# MCU.net
KiCad netlist of a schematic drawn in Altium Designer
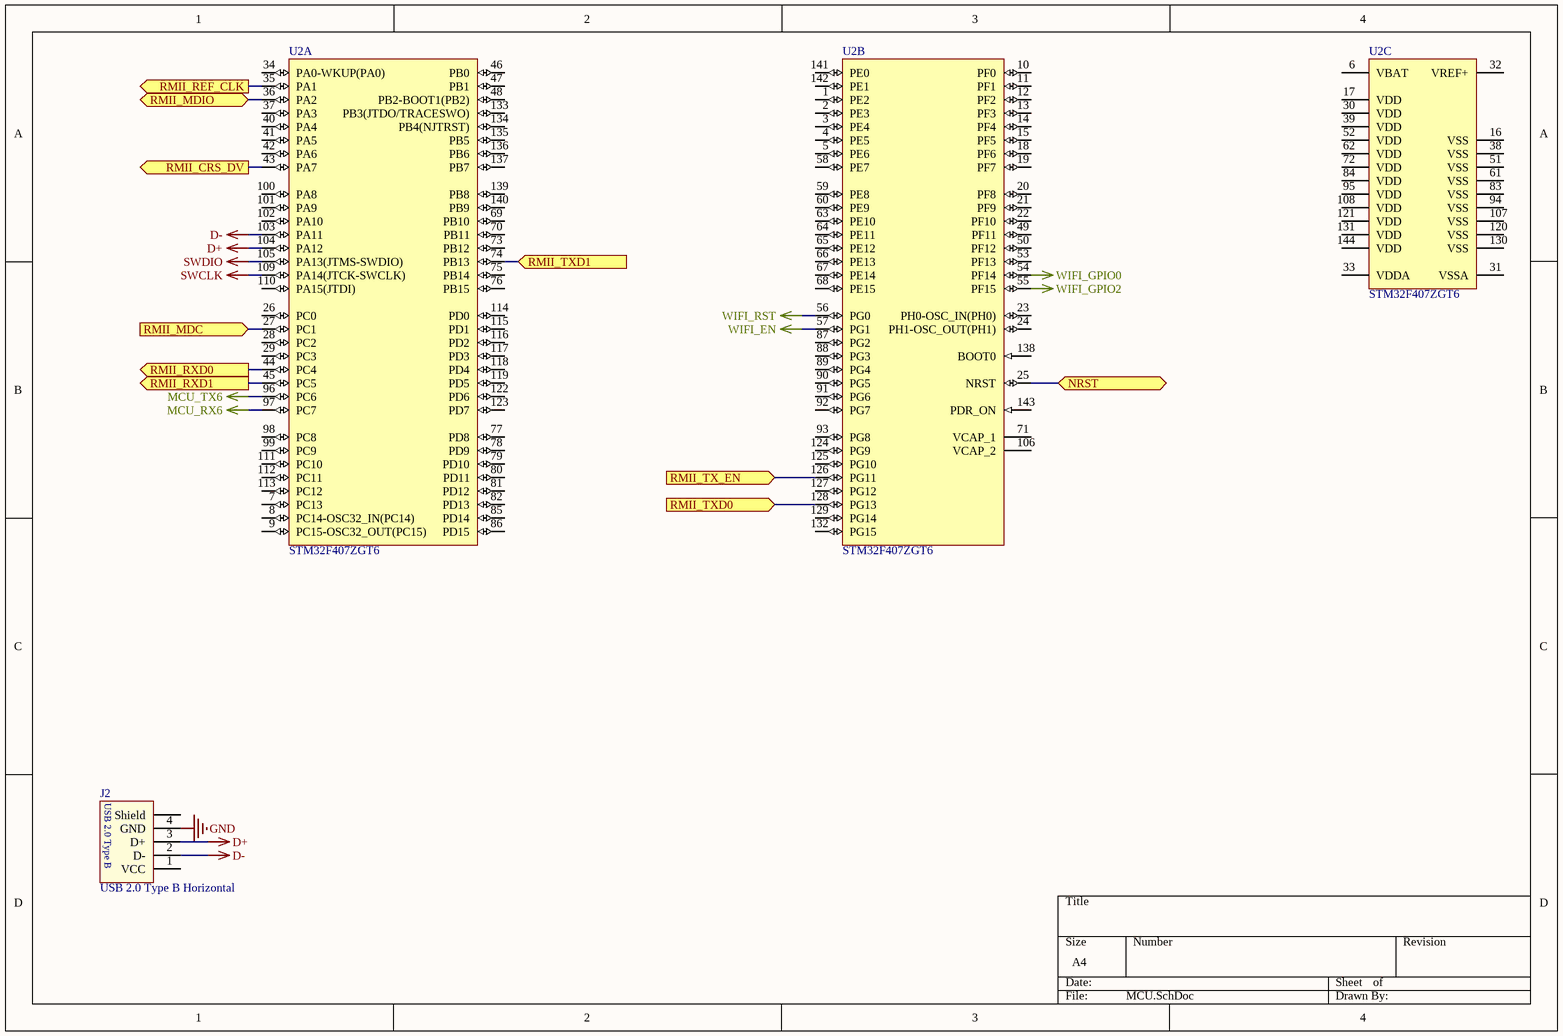
[diagram p0: MCU.SchDoc]

(export (version "E")
  (design (tool "Eeschema 10.0.6"))
  (components
    (comp (ref "J2")
      (value "USB 2.0 Type B Horizontal")
      (footprint "61400416121")
      (description "USB 2.0 Type B Horizontal WR-COM")
      (fields (field (name "PART NUMBER") "61400416121") (field (name "PUBLISHER") "Wurth Elektronik"))
      (libsource (lib "USB&HDMI") (part "USB 2.0 Type B Horizontal"))
    )
    (comp (ref "U2")
      (value "STM32F407ZGT6")
      (footprint "STM-LQFP144_N")
      (fields (field (name "MANUFACTURER") "STMicroelectronics"))
      (libsource (lib "STMicroelectronics STM32 F4") (part "STM32F407ZGT6"))
    )
  )
  (nets
    (net (code "1") (name "/NRST") (class "Default")
      (node (ref "U2") (pin "25") (pinfunction "NRST_25") (pintype "bidirectional"))
    )
    (net (code "2") (name "/RMII_CRS_DV") (class "Default")
      (node (ref "U2") (pin "43") (pinfunction "PA7_43") (pintype "bidirectional"))
    )
    (net (code "3") (name "/RMII_MDC") (class "Default")
      (node (ref "U2") (pin "27") (pinfunction "PC1_27") (pintype "bidirectional"))
    )
    (net (code "4") (name "/RMII_MDIO") (class "Default")
      (node (ref "U2") (pin "36") (pinfunction "PA2_36") (pintype "bidirectional"))
    )
    (net (code "5") (name "/RMII_REF_CLK") (class "Default")
      (node (ref "U2") (pin "35") (pinfunction "PA1_35") (pintype "bidirectional"))
    )
    (net (code "6") (name "/RMII_RXD0") (class "Default")
      (node (ref "U2") (pin "44") (pinfunction "PC4_44") (pintype "bidirectional"))
    )
    (net (code "7") (name "/RMII_RXD1") (class "Default")
      (node (ref "U2") (pin "45") (pinfunction "PC5_45") (pintype "bidirectional"))
    )
    (net (code "8") (name "/RMII_TXD0") (class "Default")
      (node (ref "U2") (pin "128") (pinfunction "PG13_128") (pintype "bidirectional"))
    )
    (net (code "9") (name "/RMII_TXD1") (class "Default")
      (node (ref "U2") (pin "74") (pinfunction "PB13_74") (pintype "bidirectional"))
    )
    (net (code "10") (name "/RMII_TX_EN") (class "Default")
      (node (ref "U2") (pin "126") (pinfunction "PG11_126") (pintype "bidirectional"))
    )
    (net (code "11") (name "D+") (class "Default")
      (node (ref "J2") (pin "3") (pinfunction "D+_3") (pintype "passive"))
      (node (ref "U2") (pin "104") (pinfunction "PA12_104") (pintype "bidirectional"))
    )
    (net (code "12") (name "D-") (class "Default")
      (node (ref "J2") (pin "2") (pinfunction "D-_2") (pintype "passive"))
      (node (ref "U2") (pin "103") (pinfunction "PA11_103") (pintype "bidirectional"))
    )
    (net (code "13") (name "GND") (class "Default")
      (node (ref "J2") (pin "4") (pinfunction "GND_4") (pintype "passive"))
    )
    (net (code "14") (name "MCU_RX6") (class "Default")
      (node (ref "U2") (pin "97") (pinfunction "PC7_97") (pintype "bidirectional"))
    )
    (net (code "15") (name "MCU_TX6") (class "Default")
      (node (ref "U2") (pin "96") (pinfunction "PC6_96") (pintype "bidirectional"))
    )
    (net (code "16") (name "SWCLK") (class "Default")
      (node (ref "U2") (pin "109") (pinfunction "PA14(JTCK-SWCLK)_109") (pintype "bidirectional"))
    )
    (net (code "17") (name "SWDIO") (class "Default")
      (node (ref "U2") (pin "105") (pinfunction "PA13(JTMS-SWDIO)_105") (pintype "bidirectional"))
    )
    (net (code "18") (name "WIFI_EN") (class "Default")
      (node (ref "U2") (pin "57") (pinfunction "PG1_57") (pintype "bidirectional"))
    )
    (net (code "19") (name "WIFI_GPIO0") (class "Default")
      (node (ref "U2") (pin "54") (pinfunction "PF14_54") (pintype "bidirectional"))
    )
    (net (code "20") (name "WIFI_GPIO2") (class "Default")
      (node (ref "U2") (pin "55") (pinfunction "PF15_55") (pintype "bidirectional"))
    )
    (net (code "21") (name "WIFI_RST") (class "Default")
      (node (ref "U2") (pin "56") (pinfunction "PG0_56") (pintype "bidirectional"))
    )
    (net (code "22") (name "unconnected-(J2-Shield-PadShell)") (class "Default")
      (node (ref "J2") (pin "Shell") (pinfunction "Shield_Shell") (pintype "passive"))
    )
    (net (code "23") (name "unconnected-(J2-VCC-Pad1)") (class "Default")
      (node (ref "J2") (pin "1") (pinfunction "VCC_1") (pintype "passive"))
    )
    (net (code "24") (name "unconnected-(U2A-PA0-WKUP(PA0)-Pad34)") (class "Default")
      (node (ref "U2") (pin "34") (pinfunction "PA0-WKUP(PA0)_34") (pintype "bidirectional"))
    )
    (net (code "25") (name "unconnected-(U2A-PA3-Pad37)") (class "Default")
      (node (ref "U2") (pin "37") (pinfunction "PA3_37") (pintype "bidirectional"))
    )
    (net (code "26") (name "unconnected-(U2A-PA4-Pad40)") (class "Default")
      (node (ref "U2") (pin "40") (pinfunction "PA4_40") (pintype "bidirectional"))
    )
    (net (code "27") (name "unconnected-(U2A-PA5-Pad41)") (class "Default")
      (node (ref "U2") (pin "41") (pinfunction "PA5_41") (pintype "bidirectional"))
    )
    (net (code "28") (name "unconnected-(U2A-PA6-Pad42)") (class "Default")
      (node (ref "U2") (pin "42") (pinfunction "PA6_42") (pintype "bidirectional"))
    )
    (net (code "29") (name "unconnected-(U2A-PA8-Pad100)") (class "Default")
      (node (ref "U2") (pin "100") (pinfunction "PA8_100") (pintype "bidirectional"))
    )
    (net (code "30") (name "unconnected-(U2A-PA9-Pad101)") (class "Default")
      (node (ref "U2") (pin "101") (pinfunction "PA9_101") (pintype "bidirectional"))
    )
    (net (code "31") (name "unconnected-(U2A-PA10-Pad102)") (class "Default")
      (node (ref "U2") (pin "102") (pinfunction "PA10_102") (pintype "bidirectional"))
    )
    (net (code "32") (name "unconnected-(U2A-PA15(JTDI)-Pad110)") (class "Default")
      (node (ref "U2") (pin "110") (pinfunction "PA15(JTDI)_110") (pintype "bidirectional"))
    )
    (net (code "33") (name "unconnected-(U2A-PB0-Pad46)") (class "Default")
      (node (ref "U2") (pin "46") (pinfunction "PB0_46") (pintype "bidirectional"))
    )
    (net (code "34") (name "unconnected-(U2A-PB1-Pad47)") (class "Default")
      (node (ref "U2") (pin "47") (pinfunction "PB1_47") (pintype "bidirectional"))
    )
    (net (code "35") (name "unconnected-(U2A-PB2-BOOT1(PB2)-Pad48)") (class "Default")
      (node (ref "U2") (pin "48") (pinfunction "PB2-BOOT1(PB2)_48") (pintype "bidirectional"))
    )
    (net (code "36") (name "unconnected-(U2A-PB3(JTDO{slash}TRACESWO)-Pad133)") (class "Default")
      (node (ref "U2") (pin "133") (pinfunction "PB3(JTDO/TRACESWO)_133") (pintype "bidirectional"))
    )
    (net (code "37") (name "unconnected-(U2A-PB4(NJTRST)-Pad134)") (class "Default")
      (node (ref "U2") (pin "134") (pinfunction "PB4(NJTRST)_134") (pintype "bidirectional"))
    )
    (net (code "38") (name "unconnected-(U2A-PB5-Pad135)") (class "Default")
      (node (ref "U2") (pin "135") (pinfunction "PB5_135") (pintype "bidirectional"))
    )
    (net (code "39") (name "unconnected-(U2A-PB6-Pad136)") (class "Default")
      (node (ref "U2") (pin "136") (pinfunction "PB6_136") (pintype "bidirectional"))
    )
    (net (code "40") (name "unconnected-(U2A-PB7-Pad137)") (class "Default")
      (node (ref "U2") (pin "137") (pinfunction "PB7_137") (pintype "bidirectional"))
    )
    (net (code "41") (name "unconnected-(U2A-PB8-Pad139)") (class "Default")
      (node (ref "U2") (pin "139") (pinfunction "PB8_139") (pintype "bidirectional"))
    )
    (net (code "42") (name "unconnected-(U2A-PB9-Pad140)") (class "Default")
      (node (ref "U2") (pin "140") (pinfunction "PB9_140") (pintype "bidirectional"))
    )
    (net (code "43") (name "unconnected-(U2A-PB10-Pad69)") (class "Default")
      (node (ref "U2") (pin "69") (pinfunction "PB10_69") (pintype "bidirectional"))
    )
    (net (code "44") (name "unconnected-(U2A-PB11-Pad70)") (class "Default")
      (node (ref "U2") (pin "70") (pinfunction "PB11_70") (pintype "bidirectional"))
    )
    (net (code "45") (name "unconnected-(U2A-PB12-Pad73)") (class "Default")
      (node (ref "U2") (pin "73") (pinfunction "PB12_73") (pintype "bidirectional"))
    )
    (net (code "46") (name "unconnected-(U2A-PB14-Pad75)") (class "Default")
      (node (ref "U2") (pin "75") (pinfunction "PB14_75") (pintype "bidirectional"))
    )
    (net (code "47") (name "unconnected-(U2A-PB15-Pad76)") (class "Default")
      (node (ref "U2") (pin "76") (pinfunction "PB15_76") (pintype "bidirectional"))
    )
    (net (code "48") (name "unconnected-(U2A-PC0-Pad26)") (class "Default")
      (node (ref "U2") (pin "26") (pinfunction "PC0_26") (pintype "bidirectional"))
    )
    (net (code "49") (name "unconnected-(U2A-PC2-Pad28)") (class "Default")
      (node (ref "U2") (pin "28") (pinfunction "PC2_28") (pintype "bidirectional"))
    )
    (net (code "50") (name "unconnected-(U2A-PC3-Pad29)") (class "Default")
      (node (ref "U2") (pin "29") (pinfunction "PC3_29") (pintype "bidirectional"))
    )
    (net (code "51") (name "unconnected-(U2A-PC8-Pad98)") (class "Default")
      (node (ref "U2") (pin "98") (pinfunction "PC8_98") (pintype "bidirectional"))
    )
    (net (code "52") (name "unconnected-(U2A-PC9-Pad99)") (class "Default")
      (node (ref "U2") (pin "99") (pinfunction "PC9_99") (pintype "bidirectional"))
    )
    (net (code "53") (name "unconnected-(U2A-PC10-Pad111)") (class "Default")
      (node (ref "U2") (pin "111") (pinfunction "PC10_111") (pintype "bidirectional"))
    )
    (net (code "54") (name "unconnected-(U2A-PC11-Pad112)") (class "Default")
      (node (ref "U2") (pin "112") (pinfunction "PC11_112") (pintype "bidirectional"))
    )
    (net (code "55") (name "unconnected-(U2A-PC12-Pad113)") (class "Default")
      (node (ref "U2") (pin "113") (pinfunction "PC12_113") (pintype "bidirectional"))
    )
    (net (code "56") (name "unconnected-(U2A-PC13-Pad7)") (class "Default")
      (node (ref "U2") (pin "7") (pinfunction "PC13_7") (pintype "bidirectional"))
    )
    (net (code "57") (name "unconnected-(U2A-PC14-OSC32_IN(PC14)-Pad8)") (class "Default")
      (node (ref "U2") (pin "8") (pinfunction "PC14-OSC32_IN(PC14)_8") (pintype "bidirectional"))
    )
    (net (code "58") (name "unconnected-(U2A-PC15-OSC32_OUT(PC15)-Pad9)") (class "Default")
      (node (ref "U2") (pin "9") (pinfunction "PC15-OSC32_OUT(PC15)_9") (pintype "bidirectional"))
    )
    (net (code "59") (name "unconnected-(U2A-PD0-Pad114)") (class "Default")
      (node (ref "U2") (pin "114") (pinfunction "PD0_114") (pintype "bidirectional"))
    )
    (net (code "60") (name "unconnected-(U2A-PD1-Pad115)") (class "Default")
      (node (ref "U2") (pin "115") (pinfunction "PD1_115") (pintype "bidirectional"))
    )
    (net (code "61") (name "unconnected-(U2A-PD2-Pad116)") (class "Default")
      (node (ref "U2") (pin "116") (pinfunction "PD2_116") (pintype "bidirectional"))
    )
    (net (code "62") (name "unconnected-(U2A-PD3-Pad117)") (class "Default")
      (node (ref "U2") (pin "117") (pinfunction "PD3_117") (pintype "bidirectional"))
    )
    (net (code "63") (name "unconnected-(U2A-PD4-Pad118)") (class "Default")
      (node (ref "U2") (pin "118") (pinfunction "PD4_118") (pintype "bidirectional"))
    )
    (net (code "64") (name "unconnected-(U2A-PD5-Pad119)") (class "Default")
      (node (ref "U2") (pin "119") (pinfunction "PD5_119") (pintype "bidirectional"))
    )
    (net (code "65") (name "unconnected-(U2A-PD6-Pad122)") (class "Default")
      (node (ref "U2") (pin "122") (pinfunction "PD6_122") (pintype "bidirectional"))
    )
    (net (code "66") (name "unconnected-(U2A-PD7-Pad123)") (class "Default")
      (node (ref "U2") (pin "123") (pinfunction "PD7_123") (pintype "bidirectional"))
    )
    (net (code "67") (name "unconnected-(U2A-PD8-Pad77)") (class "Default")
      (node (ref "U2") (pin "77") (pinfunction "PD8_77") (pintype "bidirectional"))
    )
    (net (code "68") (name "unconnected-(U2A-PD9-Pad78)") (class "Default")
      (node (ref "U2") (pin "78") (pinfunction "PD9_78") (pintype "bidirectional"))
    )
    (net (code "69") (name "unconnected-(U2A-PD10-Pad79)") (class "Default")
      (node (ref "U2") (pin "79") (pinfunction "PD10_79") (pintype "bidirectional"))
    )
    (net (code "70") (name "unconnected-(U2A-PD11-Pad80)") (class "Default")
      (node (ref "U2") (pin "80") (pinfunction "PD11_80") (pintype "bidirectional"))
    )
    (net (code "71") (name "unconnected-(U2A-PD12-Pad81)") (class "Default")
      (node (ref "U2") (pin "81") (pinfunction "PD12_81") (pintype "bidirectional"))
    )
    (net (code "72") (name "unconnected-(U2A-PD13-Pad82)") (class "Default")
      (node (ref "U2") (pin "82") (pinfunction "PD13_82") (pintype "bidirectional"))
    )
    (net (code "73") (name "unconnected-(U2A-PD14-Pad85)") (class "Default")
      (node (ref "U2") (pin "85") (pinfunction "PD14_85") (pintype "bidirectional"))
    )
    (net (code "74") (name "unconnected-(U2A-PD15-Pad86)") (class "Default")
      (node (ref "U2") (pin "86") (pinfunction "PD15_86") (pintype "bidirectional"))
    )
    (net (code "75") (name "unconnected-(U2B-BOOT0-Pad138)") (class "Default")
      (node (ref "U2") (pin "138") (pinfunction "BOOT0_138") (pintype "input"))
    )
    (net (code "76") (name "unconnected-(U2B-PDR_ON-Pad143)") (class "Default")
      (node (ref "U2") (pin "143") (pinfunction "PDR_ON_143") (pintype "input"))
    )
    (net (code "77") (name "unconnected-(U2B-PE0-Pad141)") (class "Default")
      (node (ref "U2") (pin "141") (pinfunction "PE0_141") (pintype "bidirectional"))
    )
    (net (code "78") (name "unconnected-(U2B-PE1-Pad142)") (class "Default")
      (node (ref "U2") (pin "142") (pinfunction "PE1_142") (pintype "bidirectional"))
    )
    (net (code "79") (name "unconnected-(U2B-PE2-Pad1)") (class "Default")
      (node (ref "U2") (pin "1") (pinfunction "PE2_1") (pintype "bidirectional"))
    )
    (net (code "80") (name "unconnected-(U2B-PE3-Pad2)") (class "Default")
      (node (ref "U2") (pin "2") (pinfunction "PE3_2") (pintype "bidirectional"))
    )
    (net (code "81") (name "unconnected-(U2B-PE4-Pad3)") (class "Default")
      (node (ref "U2") (pin "3") (pinfunction "PE4_3") (pintype "bidirectional"))
    )
    (net (code "82") (name "unconnected-(U2B-PE5-Pad4)") (class "Default")
      (node (ref "U2") (pin "4") (pinfunction "PE5_4") (pintype "bidirectional"))
    )
    (net (code "83") (name "unconnected-(U2B-PE6-Pad5)") (class "Default")
      (node (ref "U2") (pin "5") (pinfunction "PE6_5") (pintype "bidirectional"))
    )
    (net (code "84") (name "unconnected-(U2B-PE7-Pad58)") (class "Default")
      (node (ref "U2") (pin "58") (pinfunction "PE7_58") (pintype "bidirectional"))
    )
    (net (code "85") (name "unconnected-(U2B-PE8-Pad59)") (class "Default")
      (node (ref "U2") (pin "59") (pinfunction "PE8_59") (pintype "bidirectional"))
    )
    (net (code "86") (name "unconnected-(U2B-PE9-Pad60)") (class "Default")
      (node (ref "U2") (pin "60") (pinfunction "PE9_60") (pintype "bidirectional"))
    )
    (net (code "87") (name "unconnected-(U2B-PE10-Pad63)") (class "Default")
      (node (ref "U2") (pin "63") (pinfunction "PE10_63") (pintype "bidirectional"))
    )
    (net (code "88") (name "unconnected-(U2B-PE11-Pad64)") (class "Default")
      (node (ref "U2") (pin "64") (pinfunction "PE11_64") (pintype "bidirectional"))
    )
    (net (code "89") (name "unconnected-(U2B-PE12-Pad65)") (class "Default")
      (node (ref "U2") (pin "65") (pinfunction "PE12_65") (pintype "bidirectional"))
    )
    (net (code "90") (name "unconnected-(U2B-PE13-Pad66)") (class "Default")
      (node (ref "U2") (pin "66") (pinfunction "PE13_66") (pintype "bidirectional"))
    )
    (net (code "91") (name "unconnected-(U2B-PE14-Pad67)") (class "Default")
      (node (ref "U2") (pin "67") (pinfunction "PE14_67") (pintype "bidirectional"))
    )
    (net (code "92") (name "unconnected-(U2B-PE15-Pad68)") (class "Default")
      (node (ref "U2") (pin "68") (pinfunction "PE15_68") (pintype "bidirectional"))
    )
    (net (code "93") (name "unconnected-(U2B-PF0-Pad10)") (class "Default")
      (node (ref "U2") (pin "10") (pinfunction "PF0_10") (pintype "bidirectional"))
    )
    (net (code "94") (name "unconnected-(U2B-PF1-Pad11)") (class "Default")
      (node (ref "U2") (pin "11") (pinfunction "PF1_11") (pintype "bidirectional"))
    )
    (net (code "95") (name "unconnected-(U2B-PF2-Pad12)") (class "Default")
      (node (ref "U2") (pin "12") (pinfunction "PF2_12") (pintype "bidirectional"))
    )
    (net (code "96") (name "unconnected-(U2B-PF3-Pad13)") (class "Default")
      (node (ref "U2") (pin "13") (pinfunction "PF3_13") (pintype "bidirectional"))
    )
    (net (code "97") (name "unconnected-(U2B-PF4-Pad14)") (class "Default")
      (node (ref "U2") (pin "14") (pinfunction "PF4_14") (pintype "bidirectional"))
    )
    (net (code "98") (name "unconnected-(U2B-PF5-Pad15)") (class "Default")
      (node (ref "U2") (pin "15") (pinfunction "PF5_15") (pintype "bidirectional"))
    )
    (net (code "99") (name "unconnected-(U2B-PF6-Pad18)") (class "Default")
      (node (ref "U2") (pin "18") (pinfunction "PF6_18") (pintype "bidirectional"))
    )
    (net (code "100") (name "unconnected-(U2B-PF7-Pad19)") (class "Default")
      (node (ref "U2") (pin "19") (pinfunction "PF7_19") (pintype "bidirectional"))
    )
    (net (code "101") (name "unconnected-(U2B-PF8-Pad20)") (class "Default")
      (node (ref "U2") (pin "20") (pinfunction "PF8_20") (pintype "bidirectional"))
    )
    (net (code "102") (name "unconnected-(U2B-PF9-Pad21)") (class "Default")
      (node (ref "U2") (pin "21") (pinfunction "PF9_21") (pintype "bidirectional"))
    )
    (net (code "103") (name "unconnected-(U2B-PF10-Pad22)") (class "Default")
      (node (ref "U2") (pin "22") (pinfunction "PF10_22") (pintype "bidirectional"))
    )
    (net (code "104") (name "unconnected-(U2B-PF11-Pad49)") (class "Default")
      (node (ref "U2") (pin "49") (pinfunction "PF11_49") (pintype "bidirectional"))
    )
    (net (code "105") (name "unconnected-(U2B-PF12-Pad50)") (class "Default")
      (node (ref "U2") (pin "50") (pinfunction "PF12_50") (pintype "bidirectional"))
    )
    (net (code "106") (name "unconnected-(U2B-PF13-Pad53)") (class "Default")
      (node (ref "U2") (pin "53") (pinfunction "PF13_53") (pintype "bidirectional"))
    )
    (net (code "107") (name "unconnected-(U2B-PG2-Pad87)") (class "Default")
      (node (ref "U2") (pin "87") (pinfunction "PG2_87") (pintype "bidirectional"))
    )
    (net (code "108") (name "unconnected-(U2B-PG3-Pad88)") (class "Default")
      (node (ref "U2") (pin "88") (pinfunction "PG3_88") (pintype "bidirectional"))
    )
    (net (code "109") (name "unconnected-(U2B-PG4-Pad89)") (class "Default")
      (node (ref "U2") (pin "89") (pinfunction "PG4_89") (pintype "bidirectional"))
    )
    (net (code "110") (name "unconnected-(U2B-PG5-Pad90)") (class "Default")
      (node (ref "U2") (pin "90") (pinfunction "PG5_90") (pintype "bidirectional"))
    )
    (net (code "111") (name "unconnected-(U2B-PG6-Pad91)") (class "Default")
      (node (ref "U2") (pin "91") (pinfunction "PG6_91") (pintype "bidirectional"))
    )
    (net (code "112") (name "unconnected-(U2B-PG7-Pad92)") (class "Default")
      (node (ref "U2") (pin "92") (pinfunction "PG7_92") (pintype "bidirectional"))
    )
    (net (code "113") (name "unconnected-(U2B-PG8-Pad93)") (class "Default")
      (node (ref "U2") (pin "93") (pinfunction "PG8_93") (pintype "bidirectional"))
    )
    (net (code "114") (name "unconnected-(U2B-PG9-Pad124)") (class "Default")
      (node (ref "U2") (pin "124") (pinfunction "PG9_124") (pintype "bidirectional"))
    )
    (net (code "115") (name "unconnected-(U2B-PG10-Pad125)") (class "Default")
      (node (ref "U2") (pin "125") (pinfunction "PG10_125") (pintype "bidirectional"))
    )
    (net (code "116") (name "unconnected-(U2B-PG12-Pad127)") (class "Default")
      (node (ref "U2") (pin "127") (pinfunction "PG12_127") (pintype "bidirectional"))
    )
    (net (code "117") (name "unconnected-(U2B-PG14-Pad129)") (class "Default")
      (node (ref "U2") (pin "129") (pinfunction "PG14_129") (pintype "bidirectional"))
    )
    (net (code "118") (name "unconnected-(U2B-PG15-Pad132)") (class "Default")
      (node (ref "U2") (pin "132") (pinfunction "PG15_132") (pintype "bidirectional"))
    )
    (net (code "119") (name "unconnected-(U2B-PH0-OSC_IN(PH0)-Pad23)") (class "Default")
      (node (ref "U2") (pin "23") (pinfunction "PH0-OSC_IN(PH0)_23") (pintype "bidirectional"))
    )
    (net (code "120") (name "unconnected-(U2B-PH1-OSC_OUT(PH1)-Pad24)") (class "Default")
      (node (ref "U2") (pin "24") (pinfunction "PH1-OSC_OUT(PH1)_24") (pintype "bidirectional"))
    )
    (net (code "121") (name "unconnected-(U2B-VCAP_1-Pad71)") (class "Default")
      (node (ref "U2") (pin "71") (pinfunction "VCAP_1_71") (pintype "power_in"))
    )
    (net (code "122") (name "unconnected-(U2B-VCAP_2-Pad106)") (class "Default")
      (node (ref "U2") (pin "106") (pinfunction "VCAP_2_106") (pintype "power_in"))
    )
    (net (code "123") (name "unconnected-(U2C-VBAT-Pad6)") (class "Default")
      (node (ref "U2") (pin "6") (pinfunction "VBAT_6") (pintype "power_in"))
    )
    (net (code "124") (name "unconnected-(U2C-VDD-Pad17)") (class "Default")
      (node (ref "U2") (pin "17") (pinfunction "VDD_17") (pintype "power_in"))
    )
    (net (code "125") (name "unconnected-(U2C-VDD-Pad30)") (class "Default")
      (node (ref "U2") (pin "30") (pinfunction "VDD_30") (pintype "power_in"))
    )
    (net (code "126") (name "unconnected-(U2C-VDD-Pad39)") (class "Default")
      (node (ref "U2") (pin "39") (pinfunction "VDD_39") (pintype "power_in"))
    )
    (net (code "127") (name "unconnected-(U2C-VDD-Pad52)") (class "Default")
      (node (ref "U2") (pin "52") (pinfunction "VDD_52") (pintype "power_in"))
    )
    (net (code "128") (name "unconnected-(U2C-VDD-Pad62)") (class "Default")
      (node (ref "U2") (pin "62") (pinfunction "VDD_62") (pintype "power_in"))
    )
    (net (code "129") (name "unconnected-(U2C-VDD-Pad72)") (class "Default")
      (node (ref "U2") (pin "72") (pinfunction "VDD_72") (pintype "power_in"))
    )
    (net (code "130") (name "unconnected-(U2C-VDD-Pad84)") (class "Default")
      (node (ref "U2") (pin "84") (pinfunction "VDD_84") (pintype "power_in"))
    )
    (net (code "131") (name "unconnected-(U2C-VDD-Pad95)") (class "Default")
      (node (ref "U2") (pin "95") (pinfunction "VDD_95") (pintype "power_in"))
    )
    (net (code "132") (name "unconnected-(U2C-VDD-Pad108)") (class "Default")
      (node (ref "U2") (pin "108") (pinfunction "VDD_108") (pintype "power_in"))
    )
    (net (code "133") (name "unconnected-(U2C-VDD-Pad121)") (class "Default")
      (node (ref "U2") (pin "121") (pinfunction "VDD_121") (pintype "power_in"))
    )
    (net (code "134") (name "unconnected-(U2C-VDD-Pad131)") (class "Default")
      (node (ref "U2") (pin "131") (pinfunction "VDD_131") (pintype "power_in"))
    )
    (net (code "135") (name "unconnected-(U2C-VDD-Pad144)") (class "Default")
      (node (ref "U2") (pin "144") (pinfunction "VDD_144") (pintype "power_in"))
    )
    (net (code "136") (name "unconnected-(U2C-VDDA-Pad33)") (class "Default")
      (node (ref "U2") (pin "33") (pinfunction "VDDA_33") (pintype "power_in"))
    )
    (net (code "137") (name "unconnected-(U2C-VREF+-Pad32)") (class "Default")
      (node (ref "U2") (pin "32") (pinfunction "VREF+_32") (pintype "power_in"))
    )
    (net (code "138") (name "unconnected-(U2C-VSS-Pad16)") (class "Default")
      (node (ref "U2") (pin "16") (pinfunction "VSS_16") (pintype "power_in"))
    )
    (net (code "139") (name "unconnected-(U2C-VSS-Pad38)") (class "Default")
      (node (ref "U2") (pin "38") (pinfunction "VSS_38") (pintype "power_in"))
    )
    (net (code "140") (name "unconnected-(U2C-VSS-Pad51)") (class "Default")
      (node (ref "U2") (pin "51") (pinfunction "VSS_51") (pintype "power_in"))
    )
    (net (code "141") (name "unconnected-(U2C-VSS-Pad61)") (class "Default")
      (node (ref "U2") (pin "61") (pinfunction "VSS_61") (pintype "power_in"))
    )
    (net (code "142") (name "unconnected-(U2C-VSS-Pad83)") (class "Default")
      (node (ref "U2") (pin "83") (pinfunction "VSS_83") (pintype "power_in"))
    )
    (net (code "143") (name "unconnected-(U2C-VSS-Pad94)") (class "Default")
      (node (ref "U2") (pin "94") (pinfunction "VSS_94") (pintype "power_in"))
    )
    (net (code "144") (name "unconnected-(U2C-VSS-Pad107)") (class "Default")
      (node (ref "U2") (pin "107") (pinfunction "VSS_107") (pintype "power_in"))
    )
    (net (code "145") (name "unconnected-(U2C-VSS-Pad120)") (class "Default")
      (node (ref "U2") (pin "120") (pinfunction "VSS_120") (pintype "power_in"))
    )
    (net (code "146") (name "unconnected-(U2C-VSS-Pad130)") (class "Default")
      (node (ref "U2") (pin "130") (pinfunction "VSS_130") (pintype "power_in"))
    )
    (net (code "147") (name "unconnected-(U2C-VSSA-Pad31)") (class "Default")
      (node (ref "U2") (pin "31") (pinfunction "VSSA_31") (pintype "power_in"))
    )
  )
)
